# Sensore.net
KiCad netlist of a schematic drawn in EAGLE
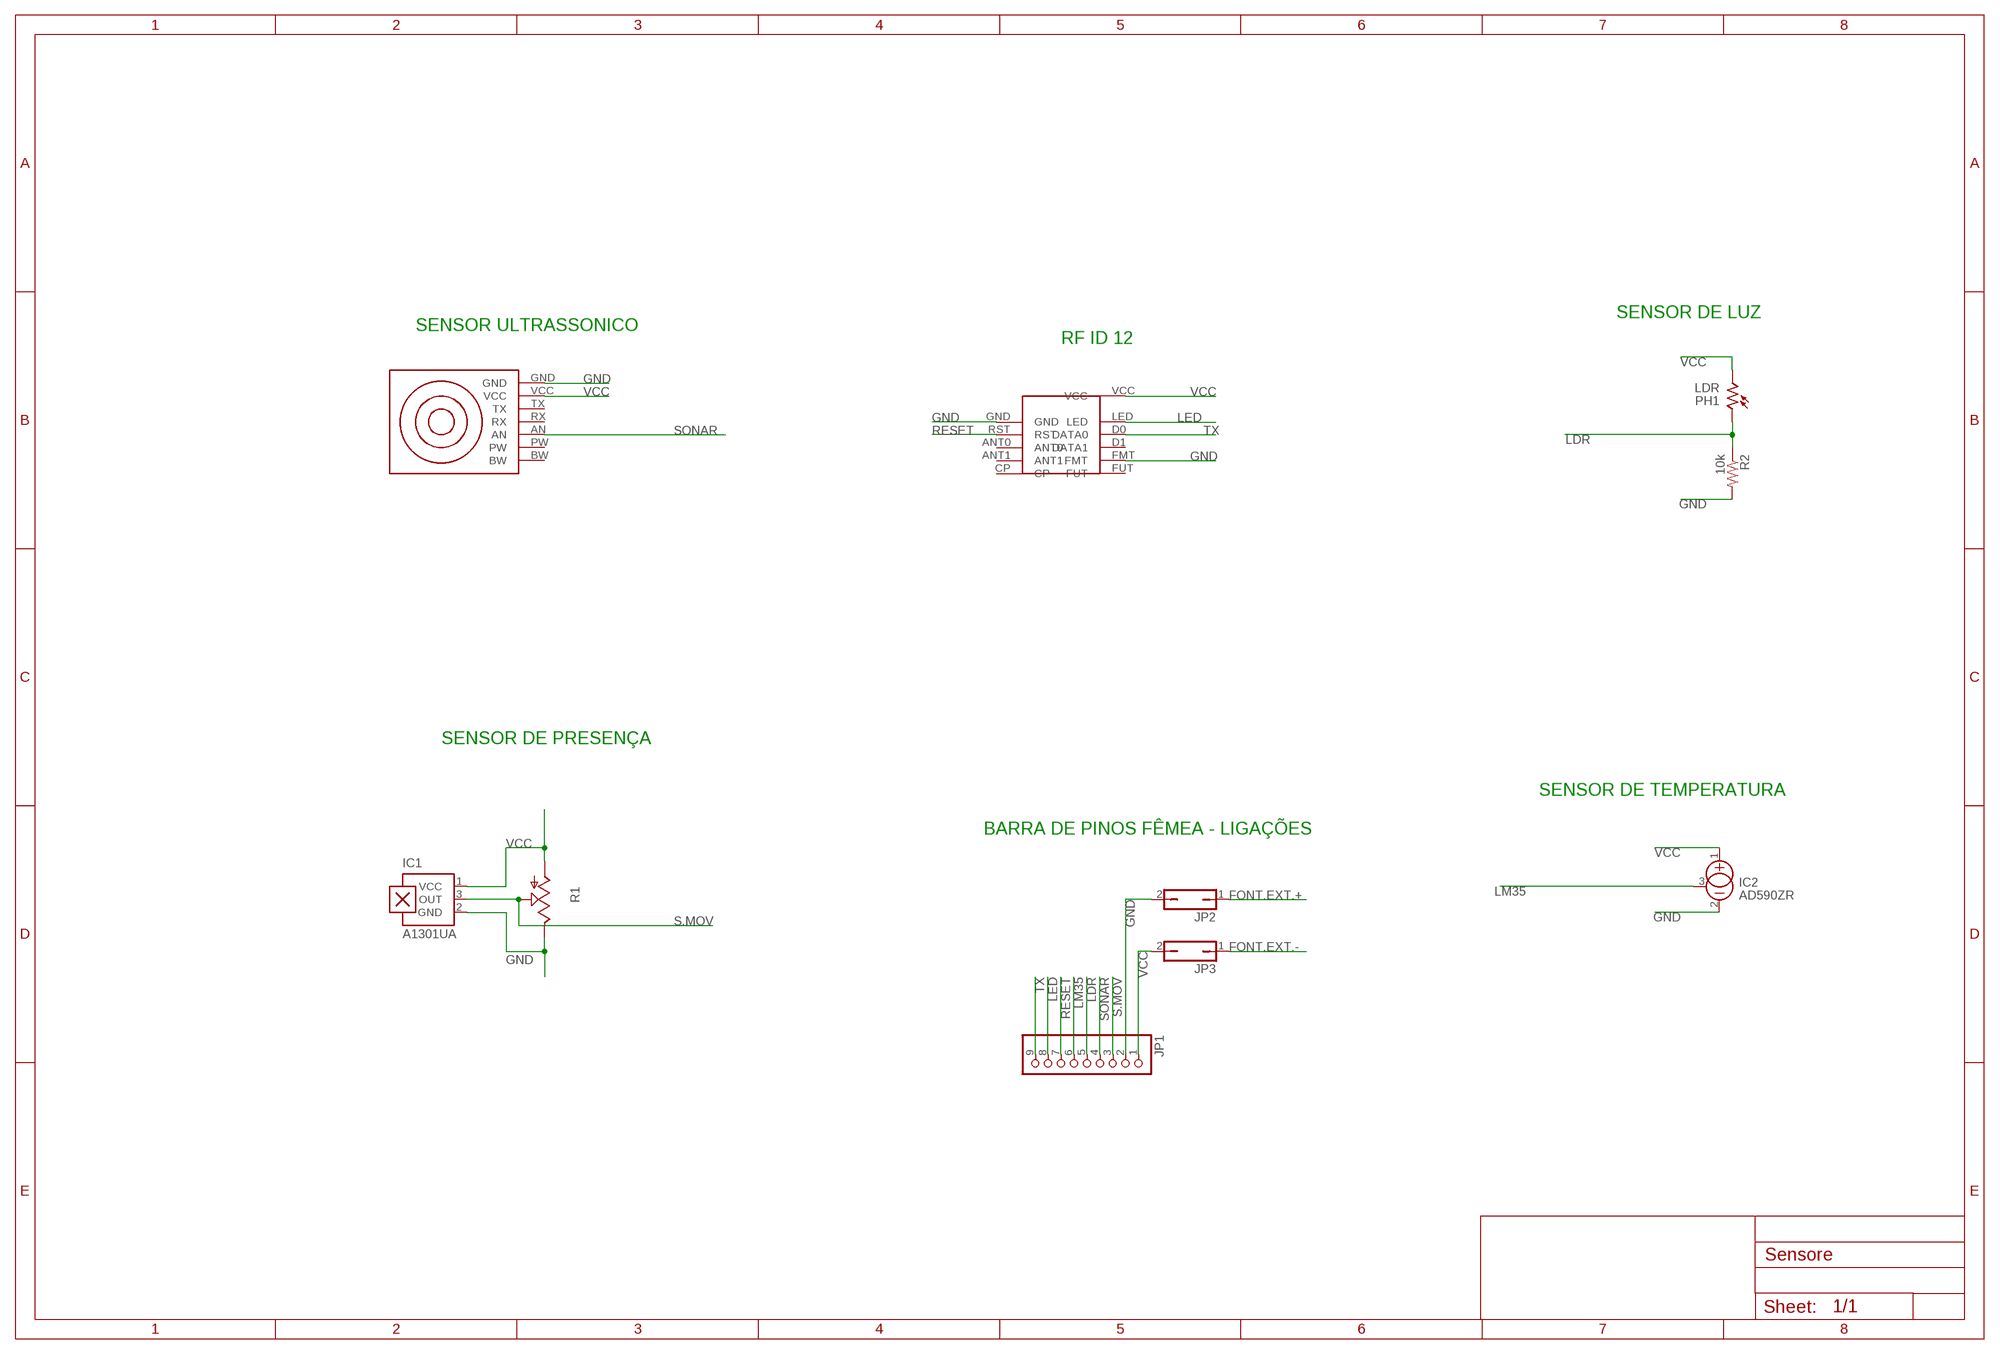
[diagram p0: schematic, sheet 1]

(export (version "E")
  (design (tool "Eeschema 10.0.6"))
  (components
    (comp (ref "IC1")
      (value "A1301UA")
      (footprint "eagle-import:SIP3-UA")
      (fields (field (name "MF") "ALLEGRO MICROSYSTEMS, INC.") (field (name "MPN") "A1301EUA-T"))
      (libsource (lib "eagle-import") (part "A13?UA01"))
    )
    (comp (ref "IC2")
      (value "AD590ZR")
      (footprint "eagle-import:TO92")
      (libsource (lib "eagle-import") (part "AD590ZR"))
    )
    (comp (ref "JP1")
      (value "PINHD-1X9")
      (footprint "eagle-import:1X09")
      (libsource (lib "eagle-import") (part "PINHD-1X9"))
    )
    (comp (ref "JP2")
      (value "JP1Q")
      (footprint "eagle-import:JP1")
      (libsource (lib "eagle-import") (part "JP1Q"))
    )
    (comp (ref "JP3")
      (value "JP1Q")
      (footprint "eagle-import:JP1")
      (libsource (lib "eagle-import") (part "JP1Q"))
    )
    (comp (ref "PH1")
      (value "LDR")
      (footprint "eagle-import:T0-46-A10XX")
      (libsource (lib "eagle-import") (part "A1050_09"))
    )
    (comp (ref "R1")
      (value "TRIM_US-CIP20C-6MM")
      (footprint "eagle-import:CIP20C-6MM")
      (libsource (lib "eagle-import") (part "TRIM_US-CIP20C-6MM"))
    )
    (comp (ref "R2")
      (value "10k")
      (footprint "eagle-import:0207_10")
      (libsource (lib "eagle-import") (part "R-US_0207/10"))
    )
    (comp (ref "U$1")
      (value "LV-EZ1")
      (footprint "eagle-import:LV-EZ1")
      (libsource (lib "eagle-import") (part "LV-EZ1"))
    )
    (comp (ref "U$2")
      (value "RFID12")
      (footprint "eagle-import:RFID12")
      (libsource (lib "eagle-import") (part "RFID12"))
    )
  )
  (nets
    (net (code "1") (name "/FONT.EXT.+") (class "Default")
      (node (ref "JP2") (pin "1") (pinfunction "1_1") (pintype "passive"))
    )
    (net (code "2") (name "/FONT.EXT.-") (class "Default")
      (node (ref "JP3") (pin "1") (pinfunction "1_1") (pintype "passive"))
    )
    (net (code "3") (name "/GND") (class "Default")
      (node (ref "IC1") (pin "2") (pinfunction "GND_2") (pintype "power_in"))
      (node (ref "IC2") (pin "2") (pinfunction "-_2") (pintype "input"))
      (node (ref "JP1") (pin "2") (pinfunction "2_2") (pintype "passive"))
      (node (ref "JP2") (pin "2") (pinfunction "2_2") (pintype "passive"))
      (node (ref "R1") (pin "E") (pinfunction "E_E") (pintype "passive"))
      (node (ref "R2") (pin "2") (pinfunction "2_2") (pintype "passive"))
      (node (ref "U$1") (pin "GND") (pinfunction "GND_GND") (pintype "bidirectional"))
      (node (ref "U$2") (pin "FMT") (pinfunction "FMT_FMT") (pintype "bidirectional"))
      (node (ref "U$2") (pin "GND") (pinfunction "GND_GND") (pintype "bidirectional"))
    )
    (net (code "4") (name "/LDR") (class "Default")
      (node (ref "JP1") (pin "5") (pinfunction "5_5") (pintype "passive"))
      (node (ref "PH1") (pin "1") (pinfunction "1_1") (pintype "passive"))
      (node (ref "R2") (pin "1") (pinfunction "1_1") (pintype "passive"))
    )
    (net (code "5") (name "/LED") (class "Default")
      (node (ref "JP1") (pin "8") (pinfunction "8_8") (pintype "passive"))
      (node (ref "U$2") (pin "LED") (pinfunction "LED_LED") (pintype "bidirectional"))
    )
    (net (code "6") (name "/LM35") (class "Default")
      (node (ref "IC2") (pin "3") (pinfunction "CAN_3") (pintype "passive"))
      (node (ref "JP1") (pin "6") (pinfunction "6_6") (pintype "passive"))
    )
    (net (code "7") (name "/RESET") (class "Default")
      (node (ref "JP1") (pin "7") (pinfunction "7_7") (pintype "passive"))
      (node (ref "U$2") (pin "RST") (pinfunction "RST_RST") (pintype "bidirectional"))
    )
    (net (code "8") (name "/S.MOV") (class "Default")
      (node (ref "IC1") (pin "3") (pinfunction "OUT_3") (pintype "output"))
      (node (ref "JP1") (pin "3") (pinfunction "3_3") (pintype "passive"))
      (node (ref "R1") (pin "S") (pinfunction "S_S") (pintype "passive"))
    )
    (net (code "9") (name "/SONAR") (class "Default")
      (node (ref "JP1") (pin "4") (pinfunction "4_4") (pintype "passive"))
      (node (ref "U$1") (pin "AN") (pinfunction "AN_AN") (pintype "bidirectional"))
    )
    (net (code "10") (name "/TX") (class "Default")
      (node (ref "JP1") (pin "9") (pinfunction "9_9") (pintype "passive"))
      (node (ref "U$2") (pin "D0") (pinfunction "DATA0_D0") (pintype "bidirectional"))
    )
    (net (code "11") (name "/VCC") (class "Default")
      (node (ref "IC1") (pin "1") (pinfunction "VCC_1") (pintype "power_in"))
      (node (ref "IC2") (pin "1") (pinfunction "+_1") (pintype "input"))
      (node (ref "JP1") (pin "1") (pinfunction "1_1") (pintype "passive"))
      (node (ref "JP3") (pin "2") (pinfunction "2_2") (pintype "passive"))
      (node (ref "PH1") (pin "2") (pinfunction "2_2") (pintype "passive"))
      (node (ref "R1") (pin "A") (pinfunction "A_A") (pintype "passive"))
      (node (ref "U$1") (pin "VCC") (pinfunction "VCC_VCC") (pintype "bidirectional"))
      (node (ref "U$2") (pin "VCC") (pinfunction "VCC_VCC") (pintype "bidirectional"))
    )
    (net (code "12") (name "unconnected-(U$1-PadBW)") (class "Default")
      (node (ref "U$1") (pin "BW") (pinfunction "BW_BW") (pintype "bidirectional"))
    )
    (net (code "13") (name "unconnected-(U$1-PadPW)") (class "Default")
      (node (ref "U$1") (pin "PW") (pinfunction "PW_PW") (pintype "bidirectional"))
    )
    (net (code "14") (name "unconnected-(U$1-PadRX)") (class "Default")
      (node (ref "U$1") (pin "RX") (pinfunction "RX_RX") (pintype "bidirectional"))
    )
    (net (code "15") (name "unconnected-(U$1-PadTX)") (class "Default")
      (node (ref "U$1") (pin "TX") (pinfunction "TX_TX") (pintype "bidirectional"))
    )
    (net (code "16") (name "unconnected-(U$2-DATA1-PadD1)") (class "Default")
      (node (ref "U$2") (pin "D1") (pinfunction "DATA1_D1") (pintype "bidirectional"))
    )
    (net (code "17") (name "unconnected-(U$2-PadANT0)") (class "Default")
      (node (ref "U$2") (pin "ANT0") (pinfunction "ANT0_ANT0") (pintype "bidirectional"))
    )
    (net (code "18") (name "unconnected-(U$2-PadANT1)") (class "Default")
      (node (ref "U$2") (pin "ANT1") (pinfunction "ANT1_ANT1") (pintype "bidirectional"))
    )
    (net (code "19") (name "unconnected-(U$2-PadCP)") (class "Default")
      (node (ref "U$2") (pin "CP") (pinfunction "CP_CP") (pintype "bidirectional"))
    )
    (net (code "20") (name "unconnected-(U$2-PadFUT)") (class "Default")
      (node (ref "U$2") (pin "FUT") (pinfunction "FUT_FUT") (pintype "bidirectional"))
    )
  )
)
